# MB_RELAY.net
KiCad netlist of a schematic drawn in Altium Designer
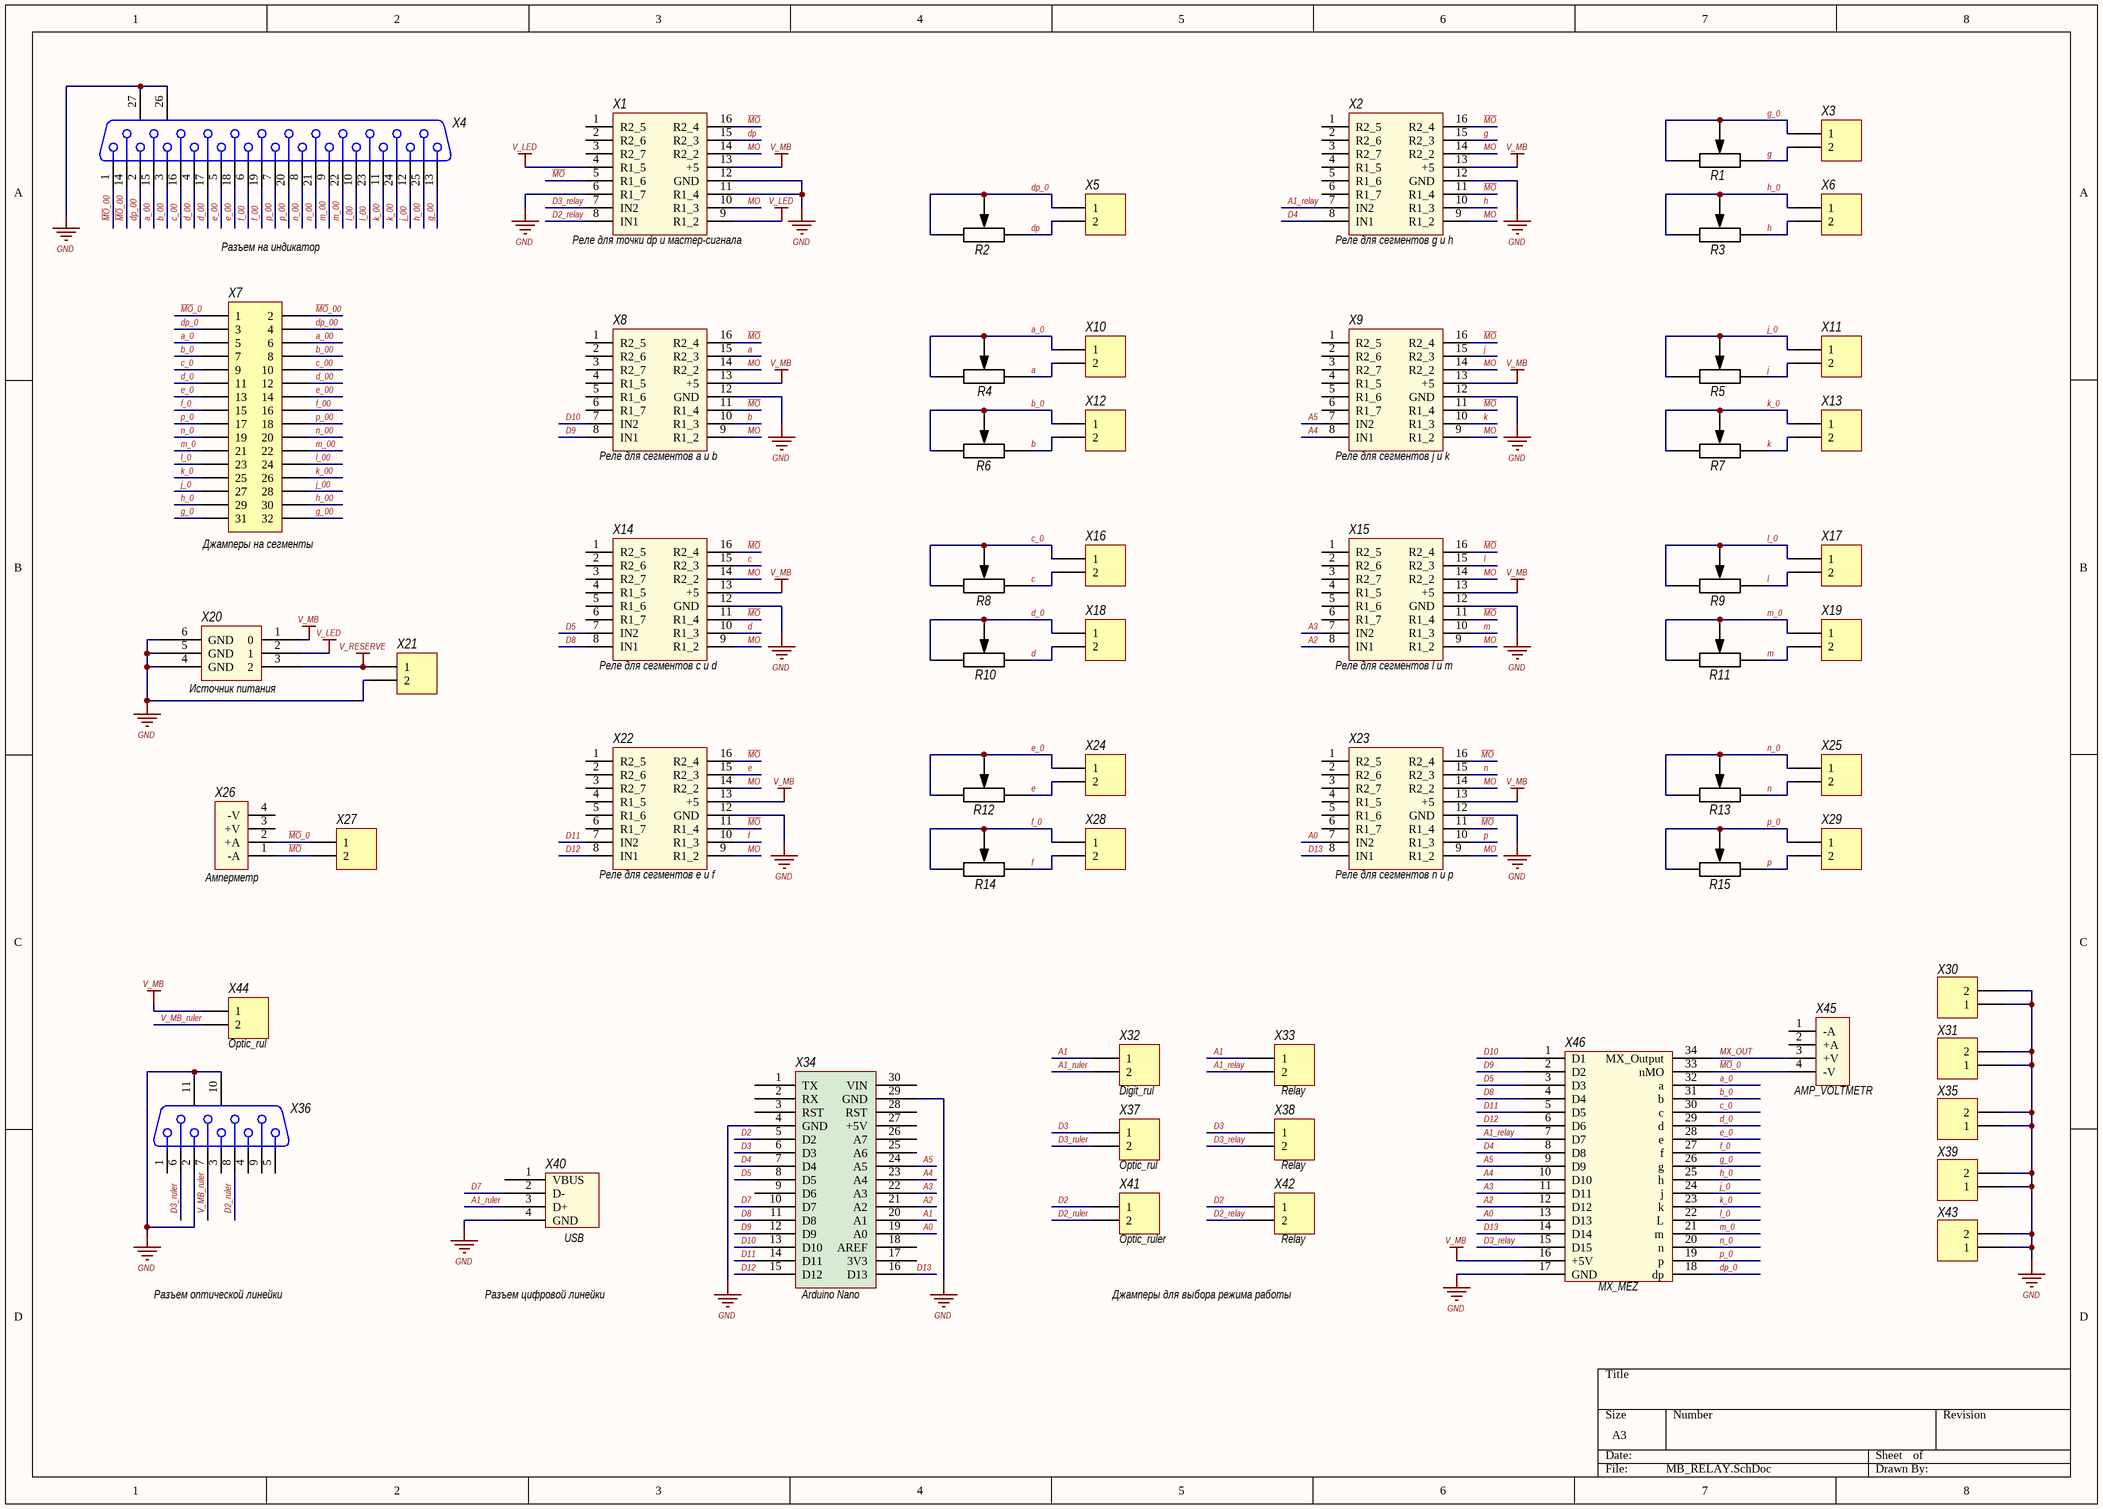
[diagram p0: MB_RELAY.SchDoc]

(export (version "E")
  (design (tool "Eeschema 10.0.6"))
  (components
    (comp (ref "R1")
      (value "RES 3266W")
      (footprint "aab_Passive:RES 3266W")
      (libsource (lib "aab_Schlib") (part "RES 3266W"))
    )
    (comp (ref "R2")
      (value "RES 3266W")
      (footprint "aab_Passive:RES 3266W")
      (libsource (lib "aab_Schlib") (part "RES 3266W"))
    )
    (comp (ref "R3")
      (value "RES 3266W")
      (footprint "aab_Passive:RES 3266W")
      (libsource (lib "aab_Schlib") (part "RES 3266W"))
    )
    (comp (ref "R4")
      (value "Переменнный резистор для")
      (footprint "aab_Passive:RES 3266W")
      (libsource (lib "aab_Schlib") (part "RES 3266W"))
    )
    (comp (ref "R5")
      (value "RES 3266W")
      (footprint "aab_Passive:RES 3266W")
      (libsource (lib "aab_Schlib") (part "RES 3266W"))
    )
    (comp (ref "R6")
      (value "RES 3266W")
      (footprint "aab_Passive:RES 3266W")
      (libsource (lib "aab_Schlib") (part "RES 3266W"))
    )
    (comp (ref "R7")
      (value "RES 3266W")
      (footprint "aab_Passive:RES 3266W")
      (libsource (lib "aab_Schlib") (part "RES 3266W"))
    )
    (comp (ref "R8")
      (value "RES 3266W")
      (footprint "aab_Passive:RES 3266W")
      (libsource (lib "aab_Schlib") (part "RES 3266W"))
    )
    (comp (ref "R9")
      (value "RES 3266W")
      (footprint "aab_Passive:RES 3266W")
      (libsource (lib "aab_Schlib") (part "RES 3266W"))
    )
    (comp (ref "R10")
      (value "RES 3266W")
      (footprint "aab_Passive:RES 3266W")
      (libsource (lib "aab_Schlib") (part "RES 3266W"))
    )
    (comp (ref "R11")
      (value "RES 3266W")
      (footprint "aab_Passive:RES 3266W")
      (libsource (lib "aab_Schlib") (part "RES 3266W"))
    )
    (comp (ref "R12")
      (value "RES 3266W")
      (footprint "aab_Passive:RES 3266W")
      (libsource (lib "aab_Schlib") (part "RES 3266W"))
    )
    (comp (ref "R13")
      (value "RES 3266W")
      (footprint "aab_Passive:RES 3266W")
      (libsource (lib "aab_Schlib") (part "RES 3266W"))
    )
    (comp (ref "R14")
      (value "RES 3266W")
      (footprint "aab_Passive:RES 3266W")
      (libsource (lib "aab_Schlib") (part "RES 3266W"))
    )
    (comp (ref "R15")
      (value "RES 3266W")
      (footprint "aab_Passive:RES 3266W")
      (libsource (lib "aab_Schlib") (part "RES 3266W"))
    )
    (comp (ref "X1")
      (value "Реле для точки dp и мастер-сигнала")
      (footprint "MEZ_RELAY")
      (libsource (lib "msp_SchLib") (part "MEZ_RELAY"))
    )
    (comp (ref "X2")
      (value "Реле для сегментов g и h")
      (footprint "MEZ_RELAY")
      (libsource (lib "msp_SchLib") (part "MEZ_RELAY"))
    )
    (comp (ref "X3")
      (value "GND")
      (footprint "HDR1X2")
      (description "Header, 2-Pin")
      (fields (field (name "PUBLISHER") "Altium Limited"))
      (libsource (lib "") (part "Header 2_1"))
    )
    (comp (ref "X4")
      (value "D Connector 25")
      (footprint "DSUB1.385-2H25A")
      (description "Receptacle Assembly, 25 Position, Right Angle")
      (fields (field (name "PUBLISHER") "Altium Limited"))
      (libsource (lib "Miscellaneous Connectors") (part "D Connector 25"))
    )
    (comp (ref "X5")
      (value "GND")
      (footprint "HDR1X2")
      (description "Header, 2-Pin")
      (fields (field (name "PUBLISHER") "Altium Limited"))
      (libsource (lib "") (part "Header 2_1"))
    )
    (comp (ref "X6")
      (value "GND")
      (footprint "HDR1X2")
      (description "Header, 2-Pin")
      (fields (field (name "PUBLISHER") "Altium Limited"))
      (libsource (lib "") (part "Header 2_1"))
    )
    (comp (ref "X7")
      (value "Header 16X2")
      (footprint "HDR2X16")
      (description "Header, 16-Pin, Dual row")
      (fields (field (name "PUBLISHER") "Altium Limited"))
      (libsource (lib "Miscellaneous Connectors") (part "Header 16X2"))
    )
    (comp (ref "X8")
      (value "Реле для сегментов a и b")
      (footprint "MEZ_RELAY")
      (libsource (lib "msp_SchLib") (part "MEZ_RELAY"))
    )
    (comp (ref "X9")
      (value "Реле для сегментов j и k")
      (footprint "MEZ_RELAY")
      (libsource (lib "msp_SchLib") (part "MEZ_RELAY"))
    )
    (comp (ref "X10")
      (value "Header 2")
      (footprint "HDR1X2")
      (description "Header, 2-Pin")
      (fields (field (name "PUBLISHER") "Altium Limited"))
      (libsource (lib "") (part "Header 2_1"))
    )
    (comp (ref "X11")
      (value "Header 2")
      (footprint "HDR1X2")
      (description "Header, 2-Pin")
      (fields (field (name "PUBLISHER") "Altium Limited"))
      (libsource (lib "") (part "Header 2_1"))
    )
    (comp (ref "X12")
      (value "Header 2")
      (footprint "HDR1X2")
      (description "Header, 2-Pin")
      (fields (field (name "PUBLISHER") "Altium Limited"))
      (libsource (lib "") (part "Header 2_1"))
    )
    (comp (ref "X13")
      (value "Header 2")
      (footprint "HDR1X2")
      (description "Header, 2-Pin")
      (fields (field (name "PUBLISHER") "Altium Limited"))
      (libsource (lib "") (part "Header 2_1"))
    )
    (comp (ref "X14")
      (value "Реле для сегментов c и d")
      (footprint "MEZ_RELAY")
      (libsource (lib "msp_SchLib") (part "MEZ_RELAY"))
    )
    (comp (ref "X15")
      (value "Реле для сегментов l и m")
      (footprint "MEZ_RELAY")
      (libsource (lib "msp_SchLib") (part "MEZ_RELAY"))
    )
    (comp (ref "X16")
      (value "Header 2")
      (footprint "HDR1X2")
      (description "Header, 2-Pin")
      (fields (field (name "PUBLISHER") "Altium Limited"))
      (libsource (lib "") (part "Header 2_1"))
    )
    (comp (ref "X17")
      (value "GND")
      (footprint "HDR1X2")
      (description "Header, 2-Pin")
      (fields (field (name "PUBLISHER") "Altium Limited"))
      (libsource (lib "") (part "Header 2_1"))
    )
    (comp (ref "X18")
      (value "Header 2")
      (footprint "HDR1X2")
      (description "Header, 2-Pin")
      (fields (field (name "PUBLISHER") "Altium Limited"))
      (libsource (lib "") (part "Header 2_1"))
    )
    (comp (ref "X19")
      (value "GND")
      (footprint "HDR1X2")
      (description "Header, 2-Pin")
      (fields (field (name "PUBLISHER") "Altium Limited"))
      (libsource (lib "") (part "Header 2_1"))
    )
    (comp (ref "X20")
      (value "Источник питания")
      (footprint "vpl_Passive:POWER")
      (libsource (lib "msp_SchLib") (part "POWER"))
    )
    (comp (ref "X21")
      (value "Header 2")
      (footprint "HDR1X2")
      (description "Header, 2-Pin")
      (fields (field (name "PUBLISHER") "Altium Limited"))
      (libsource (lib "") (part "Header 2_1"))
    )
    (comp (ref "X22")
      (value "Реле для сегментов e и f")
      (footprint "MEZ_RELAY")
      (libsource (lib "msp_SchLib") (part "MEZ_RELAY"))
    )
    (comp (ref "X23")
      (value "Реле для сегментов n и p")
      (footprint "MEZ_RELAY")
      (libsource (lib "msp_SchLib") (part "MEZ_RELAY"))
    )
    (comp (ref "X24")
      (value "GND")
      (footprint "HDR1X2")
      (description "Header, 2-Pin")
      (fields (field (name "PUBLISHER") "Altium Limited"))
      (libsource (lib "") (part "Header 2_1"))
    )
    (comp (ref "X25")
      (value "GND")
      (footprint "HDR1X2")
      (description "Header, 2-Pin")
      (fields (field (name "PUBLISHER") "Altium Limited"))
      (libsource (lib "") (part "Header 2_1"))
    )
    (comp (ref "X26")
      (value "Амперметр")
      (footprint "vpl_Passive:AMP_VOLTMETER")
      (libsource (lib "") (part "AMP_VOLTMETR_1"))
    )
    (comp (ref "X27")
      (value "Header 2")
      (footprint "HDR1X2")
      (description "Header, 2-Pin")
      (fields (field (name "PUBLISHER") "Altium Limited"))
      (libsource (lib "") (part "Header 2_1"))
    )
    (comp (ref "X28")
      (value "GND")
      (footprint "HDR1X2")
      (description "Header, 2-Pin")
      (fields (field (name "PUBLISHER") "Altium Limited"))
      (libsource (lib "") (part "Header 2_1"))
    )
    (comp (ref "X29")
      (value "GND")
      (footprint "HDR1X2")
      (description "Header, 2-Pin")
      (fields (field (name "PUBLISHER") "Altium Limited"))
      (libsource (lib "") (part "Header 2_1"))
    )
    (comp (ref "X30")
      (value "Header 2")
      (footprint "HDR1X2")
      (description "Header, 2-Pin")
      (fields (field (name "PUBLISHER") "Altium Limited"))
      (libsource (lib "Miscellaneous Connectors") (part "Header 2"))
    )
    (comp (ref "X31")
      (value "GND")
      (footprint "HDR1X2")
      (description "Header, 2-Pin")
      (fields (field (name "PUBLISHER") "Altium Limited"))
      (libsource (lib "Miscellaneous Connectors") (part "Header 2"))
    )
    (comp (ref "X32")
      (value "Digit_rul")
      (footprint "HDR1X2")
      (description "Header, 2-Pin")
      (fields (field (name "PUBLISHER") "Altium Limited"))
      (libsource (lib "") (part "Header 2_1"))
    )
    (comp (ref "X33")
      (value "Relay")
      (footprint "HDR1X2")
      (description "Header, 2-Pin")
      (fields (field (name "PUBLISHER") "Altium Limited"))
      (libsource (lib "") (part "Header 2_1"))
    )
    (comp (ref "X34")
      (value "Arduino Nano")
      (footprint "PCBComponent_1")
      (libsource (lib "Nano") (part "Component_1"))
    )
    (comp (ref "X35")
      (value "GND")
      (footprint "HDR1X2")
      (description "Header, 2-Pin")
      (fields (field (name "PUBLISHER") "Altium Limited"))
      (libsource (lib "Miscellaneous Connectors") (part "Header 2"))
    )
    (comp (ref "X36")
      (value "D Connector 9")
      (footprint "DSUB1.385-2H9")
      (description "Receptacle Assembly, 9 Position, Right Angle")
      (fields (field (name "PUBLISHER") "Altium Limited"))
      (libsource (lib "Miscellaneous Connectors") (part "D Connector 9"))
    )
    (comp (ref "X37")
      (value "Optic_rul")
      (footprint "HDR1X2")
      (description "Header, 2-Pin")
      (fields (field (name "PUBLISHER") "Altium Limited"))
      (libsource (lib "") (part "Header 2_1"))
    )
    (comp (ref "X38")
      (value "Relay")
      (footprint "HDR1X2")
      (description "Header, 2-Pin")
      (fields (field (name "PUBLISHER") "Altium Limited"))
      (libsource (lib "") (part "Header 2_1"))
    )
    (comp (ref "X39")
      (value "GND")
      (footprint "HDR1X2")
      (description "Header, 2-Pin")
      (fields (field (name "PUBLISHER") "Altium Limited"))
      (libsource (lib "Miscellaneous Connectors") (part "Header 2"))
    )
    (comp (ref "X40") (value "USB") (footprint "USB") (libsource (lib "msp_SchLib") (part "USB")))
    (comp (ref "X41")
      (value "Optic_ruler")
      (footprint "HDR1X2")
      (description "Header, 2-Pin")
      (fields (field (name "PUBLISHER") "Altium Limited"))
      (libsource (lib "") (part "Header 2_1"))
    )
    (comp (ref "X42")
      (value "Relay")
      (footprint "HDR1X2")
      (description "Header, 2-Pin")
      (fields (field (name "PUBLISHER") "Altium Limited"))
      (libsource (lib "") (part "Header 2_1"))
    )
    (comp (ref "X43")
      (value "GND")
      (footprint "HDR1X2")
      (description "Header, 2-Pin")
      (fields (field (name "PUBLISHER") "Altium Limited"))
      (libsource (lib "Miscellaneous Connectors") (part "Header 2"))
    )
    (comp (ref "X44")
      (value "Optic_rul")
      (footprint "HDR1X2")
      (description "Header, 2-Pin")
      (fields (field (name "PUBLISHER") "Altium Limited"))
      (libsource (lib "") (part "Header 2_1"))
    )
    (comp (ref "X45")
      (value "AMP_VOLTMETR")
      (footprint "AMP_VOLTMETR")
      (libsource (lib "msp_SchLib") (part "AMP_VOLTMETR"))
    )
    (comp (ref "X46") (value "MX_MEZ") (footprint "MX_MEZ") (libsource (lib "msp_SchLib") (part "MX_MEZ")))
  )
  (nets
    (net (code "1") (name "/A0") (class "Default")
      (node (ref "X23") (pin "7") (pinfunction "IN2_7") (pintype "passive"))
      (node (ref "X34") (pin "19") (pinfunction "A0_19") (pintype "passive"))
      (node (ref "X46") (pin "13") (pinfunction "D13_13") (pintype "passive"))
    )
    (net (code "2") (name "/A1") (class "Default")
      (node (ref "X32") (pin "1") (pinfunction "1_1") (pintype "passive"))
      (node (ref "X33") (pin "1") (pinfunction "1_1") (pintype "passive"))
      (node (ref "X34") (pin "20") (pinfunction "A1_20") (pintype "passive"))
    )
    (net (code "3") (name "/A1_relay") (class "Default")
      (node (ref "X2") (pin "7") (pinfunction "IN2_7") (pintype "passive"))
      (node (ref "X33") (pin "2") (pinfunction "2_2") (pintype "passive"))
      (node (ref "X46") (pin "7") (pinfunction "D7_7") (pintype "passive"))
    )
    (net (code "4") (name "/A1_ruler") (class "Default")
      (node (ref "X32") (pin "2") (pinfunction "2_2") (pintype "passive"))
      (node (ref "X40") (pin "3") (pinfunction "D+_3") (pintype "passive"))
    )
    (net (code "5") (name "/A2") (class "Default")
      (node (ref "X15") (pin "8") (pinfunction "IN1_8") (pintype "passive"))
      (node (ref "X34") (pin "21") (pinfunction "A2_21") (pintype "passive"))
      (node (ref "X46") (pin "12") (pinfunction "D12_12") (pintype "passive"))
    )
    (net (code "6") (name "/A3") (class "Default")
      (node (ref "X15") (pin "7") (pinfunction "IN2_7") (pintype "passive"))
      (node (ref "X34") (pin "22") (pinfunction "A3_22") (pintype "passive"))
      (node (ref "X46") (pin "11") (pinfunction "D11_11") (pintype "passive"))
    )
    (net (code "7") (name "/A4") (class "Default")
      (node (ref "X34") (pin "23") (pinfunction "A4_23") (pintype "passive"))
      (node (ref "X46") (pin "10") (pinfunction "D10_10") (pintype "passive"))
      (node (ref "X9") (pin "8") (pinfunction "IN1_8") (pintype "passive"))
    )
    (net (code "8") (name "/A5") (class "Default")
      (node (ref "X34") (pin "24") (pinfunction "A5_24") (pintype "passive"))
      (node (ref "X46") (pin "9") (pinfunction "D9_9") (pintype "passive"))
      (node (ref "X9") (pin "7") (pinfunction "IN2_7") (pintype "passive"))
    )
    (net (code "9") (name "/D2") (class "Default")
      (node (ref "X34") (pin "5") (pinfunction "D2_5") (pintype "passive"))
      (node (ref "X41") (pin "1") (pinfunction "1_1") (pintype "passive"))
      (node (ref "X42") (pin "1") (pinfunction "1_1") (pintype "passive"))
    )
    (net (code "10") (name "/D2_relay") (class "Default")
      (node (ref "X1") (pin "8") (pinfunction "IN1_8") (pintype "passive"))
      (node (ref "X42") (pin "2") (pinfunction "2_2") (pintype "passive"))
    )
    (net (code "11") (name "/D2_ruler") (class "Default")
      (node (ref "X36") (pin "8") (pinfunction "8_8") (pintype "passive"))
      (node (ref "X41") (pin "2") (pinfunction "2_2") (pintype "passive"))
    )
    (net (code "12") (name "/D3") (class "Default")
      (node (ref "X34") (pin "6") (pinfunction "D3_6") (pintype "passive"))
      (node (ref "X37") (pin "1") (pinfunction "1_1") (pintype "passive"))
      (node (ref "X38") (pin "1") (pinfunction "1_1") (pintype "passive"))
    )
    (net (code "13") (name "/D3_relay") (class "Default")
      (node (ref "X1") (pin "7") (pinfunction "IN2_7") (pintype "passive"))
      (node (ref "X38") (pin "2") (pinfunction "2_2") (pintype "passive"))
      (node (ref "X46") (pin "15") (pinfunction "D15_15") (pintype "passive"))
    )
    (net (code "14") (name "/D3_ruler") (class "Default")
      (node (ref "X36") (pin "6") (pinfunction "6_6") (pintype "passive"))
      (node (ref "X37") (pin "2") (pinfunction "2_2") (pintype "passive"))
    )
    (net (code "15") (name "/D4") (class "Default")
      (node (ref "X2") (pin "8") (pinfunction "IN1_8") (pintype "passive"))
      (node (ref "X34") (pin "7") (pinfunction "D4_7") (pintype "passive"))
      (node (ref "X46") (pin "8") (pinfunction "D8_8") (pintype "passive"))
    )
    (net (code "16") (name "/D5") (class "Default")
      (node (ref "X14") (pin "7") (pinfunction "IN2_7") (pintype "passive"))
      (node (ref "X34") (pin "8") (pinfunction "D5_8") (pintype "passive"))
      (node (ref "X46") (pin "3") (pinfunction "D3_3") (pintype "passive"))
    )
    (net (code "17") (name "/D7") (class "Default")
      (node (ref "X34") (pin "10") (pinfunction "D7_10") (pintype "passive"))
      (node (ref "X40") (pin "2") (pinfunction "D-_2") (pintype "passive"))
    )
    (net (code "18") (name "/D8") (class "Default")
      (node (ref "X14") (pin "8") (pinfunction "IN1_8") (pintype "passive"))
      (node (ref "X34") (pin "11") (pinfunction "D8_11") (pintype "passive"))
      (node (ref "X46") (pin "4") (pinfunction "D4_4") (pintype "passive"))
    )
    (net (code "19") (name "/D9") (class "Default")
      (node (ref "X34") (pin "12") (pinfunction "D9_12") (pintype "passive"))
      (node (ref "X46") (pin "2") (pinfunction "D2_2") (pintype "passive"))
      (node (ref "X8") (pin "8") (pinfunction "IN1_8") (pintype "passive"))
    )
    (net (code "20") (name "/D10") (class "Default")
      (node (ref "X34") (pin "13") (pinfunction "D10_13") (pintype "passive"))
      (node (ref "X46") (pin "1") (pinfunction "D1_1") (pintype "passive"))
      (node (ref "X8") (pin "7") (pinfunction "IN2_7") (pintype "passive"))
    )
    (net (code "21") (name "/D11") (class "Default")
      (node (ref "X22") (pin "7") (pinfunction "IN2_7") (pintype "passive"))
      (node (ref "X34") (pin "14") (pinfunction "D11_14") (pintype "passive"))
      (node (ref "X46") (pin "5") (pinfunction "D5_5") (pintype "passive"))
    )
    (net (code "22") (name "/D12") (class "Default")
      (node (ref "X22") (pin "8") (pinfunction "IN1_8") (pintype "passive"))
      (node (ref "X34") (pin "15") (pinfunction "D12_15") (pintype "passive"))
      (node (ref "X46") (pin "6") (pinfunction "D6_6") (pintype "passive"))
    )
    (net (code "23") (name "/D13") (class "Default")
      (node (ref "X23") (pin "8") (pinfunction "IN1_8") (pintype "passive"))
      (node (ref "X34") (pin "16") (pinfunction "D13_16") (pintype "passive"))
      (node (ref "X46") (pin "14") (pinfunction "D14_14") (pintype "passive"))
    )
    (net (code "24") (name "/MO") (class "Default")
      (node (ref "X1") (pin "10") (pinfunction "R1_3_10") (pintype "passive"))
      (node (ref "X1") (pin "14") (pinfunction "R2_2_14") (pintype "passive"))
      (node (ref "X14") (pin "14") (pinfunction "R2_2_14") (pintype "passive"))
      (node (ref "X14") (pin "9") (pinfunction "R1_2_9") (pintype "passive"))
      (node (ref "X15") (pin "14") (pinfunction "R2_2_14") (pintype "passive"))
      (node (ref "X15") (pin "9") (pinfunction "R1_2_9") (pintype "passive"))
      (node (ref "X2") (pin "14") (pinfunction "R2_2_14") (pintype "passive"))
      (node (ref "X2") (pin "9") (pinfunction "R1_2_9") (pintype "passive"))
      (node (ref "X22") (pin "14") (pinfunction "R2_2_14") (pintype "passive"))
      (node (ref "X22") (pin "9") (pinfunction "R1_2_9") (pintype "passive"))
      (node (ref "X23") (pin "14") (pinfunction "R2_2_14") (pintype "passive"))
      (node (ref "X23") (pin "9") (pinfunction "R1_2_9") (pintype "passive"))
      (node (ref "X8") (pin "14") (pinfunction "R2_2_14") (pintype "passive"))
      (node (ref "X8") (pin "9") (pinfunction "R1_2_9") (pintype "passive"))
      (node (ref "X9") (pin "14") (pinfunction "R2_2_14") (pintype "passive"))
      (node (ref "X9") (pin "9") (pinfunction "R1_2_9") (pintype "passive"))
    )
    (net (code "25") (name "/MX_OUT") (class "Default")
      (node (ref "X45") (pin "3") (pinfunction "+V_3") (pintype "passive"))
      (node (ref "X46") (pin "34") (pinfunction "MX_Output_34") (pintype "passive"))
    )
    (net (code "26") (name "/V_MB_ruler") (class "Default")
      (node (ref "X36") (pin "7") (pinfunction "7_7") (pintype "passive"))
      (node (ref "X44") (pin "2") (pinfunction "2_2") (pintype "passive"))
    )
    (net (code "27") (name "/a") (class "Default")
      (node (ref "R4") (pin "3") (pinfunction "3_3") (pintype "passive"))
      (node (ref "X10") (pin "2") (pinfunction "2_2") (pintype "passive"))
      (node (ref "X8") (pin "15") (pinfunction "R2_3_15") (pintype "passive"))
    )
    (net (code "28") (name "/a_0") (class "Default")
      (node (ref "R4") (pin "1") (pinfunction "1_1") (pintype "passive"))
      (node (ref "R4") (pin "2") (pinfunction "2_2") (pintype "passive"))
      (node (ref "X10") (pin "1") (pinfunction "1_1") (pintype "passive"))
      (node (ref "X46") (pin "32") (pinfunction "a_32") (pintype "passive"))
      (node (ref "X7") (pin "5") (pinfunction "5_5") (pintype "passive"))
    )
    (net (code "29") (name "/a_00") (class "Default")
      (node (ref "X4") (pin "15") (pinfunction "15_15") (pintype "passive"))
      (node (ref "X7") (pin "6") (pinfunction "6_6") (pintype "passive"))
    )
    (net (code "30") (name "/b") (class "Default")
      (node (ref "R6") (pin "3") (pinfunction "3_3") (pintype "passive"))
      (node (ref "X12") (pin "2") (pinfunction "2_2") (pintype "passive"))
      (node (ref "X8") (pin "10") (pinfunction "R1_3_10") (pintype "passive"))
    )
    (net (code "31") (name "/b_0") (class "Default")
      (node (ref "R6") (pin "1") (pinfunction "1_1") (pintype "passive"))
      (node (ref "R6") (pin "2") (pinfunction "2_2") (pintype "passive"))
      (node (ref "X12") (pin "1") (pinfunction "1_1") (pintype "passive"))
      (node (ref "X46") (pin "31") (pinfunction "b_31") (pintype "passive"))
      (node (ref "X7") (pin "7") (pinfunction "7_7") (pintype "passive"))
    )
    (net (code "32") (name "/b_00") (class "Default")
      (node (ref "X4") (pin "3") (pinfunction "3_3") (pintype "passive"))
      (node (ref "X7") (pin "8") (pinfunction "8_8") (pintype "passive"))
    )
    (net (code "33") (name "/c") (class "Default")
      (node (ref "R8") (pin "3") (pinfunction "3_3") (pintype "passive"))
      (node (ref "X14") (pin "15") (pinfunction "R2_3_15") (pintype "passive"))
      (node (ref "X16") (pin "2") (pinfunction "2_2") (pintype "passive"))
    )
    (net (code "34") (name "/c_0") (class "Default")
      (node (ref "R8") (pin "1") (pinfunction "1_1") (pintype "passive"))
      (node (ref "R8") (pin "2") (pinfunction "2_2") (pintype "passive"))
      (node (ref "X16") (pin "1") (pinfunction "1_1") (pintype "passive"))
      (node (ref "X46") (pin "30") (pinfunction "c_30") (pintype "passive"))
      (node (ref "X7") (pin "9") (pinfunction "9_9") (pintype "passive"))
    )
    (net (code "35") (name "/c_00") (class "Default")
      (node (ref "X4") (pin "16") (pinfunction "16_16") (pintype "passive"))
      (node (ref "X7") (pin "10") (pinfunction "10_10") (pintype "passive"))
    )
    (net (code "36") (name "/d") (class "Default")
      (node (ref "R10") (pin "3") (pinfunction "3_3") (pintype "passive"))
      (node (ref "X14") (pin "10") (pinfunction "R1_3_10") (pintype "passive"))
      (node (ref "X18") (pin "2") (pinfunction "2_2") (pintype "passive"))
    )
    (net (code "37") (name "/d_00") (class "Default")
      (node (ref "X4") (pin "17") (pinfunction "17_17") (pintype "passive"))
      (node (ref "X4") (pin "4") (pinfunction "4_4") (pintype "passive"))
      (node (ref "X7") (pin "12") (pinfunction "12_12") (pintype "passive"))
    )
    (net (code "38") (name "/d_0") (class "Default")
      (node (ref "R10") (pin "1") (pinfunction "1_1") (pintype "passive"))
      (node (ref "R10") (pin "2") (pinfunction "2_2") (pintype "passive"))
      (node (ref "X18") (pin "1") (pinfunction "1_1") (pintype "passive"))
      (node (ref "X46") (pin "29") (pinfunction "d_29") (pintype "passive"))
      (node (ref "X7") (pin "11") (pinfunction "11_11") (pintype "passive"))
    )
    (net (code "39") (name "/dp") (class "Default")
      (node (ref "R2") (pin "3") (pinfunction "3_3") (pintype "passive"))
      (node (ref "X1") (pin "15") (pinfunction "R2_3_15") (pintype "passive"))
      (node (ref "X5") (pin "2") (pinfunction "2_2") (pintype "passive"))
    )
    (net (code "40") (name "/dp_0") (class "Default")
      (node (ref "R2") (pin "1") (pinfunction "1_1") (pintype "passive"))
      (node (ref "R2") (pin "2") (pinfunction "2_2") (pintype "passive"))
      (node (ref "X46") (pin "18") (pinfunction "dp_18") (pintype "passive"))
      (node (ref "X5") (pin "1") (pinfunction "1_1") (pintype "passive"))
      (node (ref "X7") (pin "3") (pinfunction "3_3") (pintype "passive"))
    )
    (net (code "41") (name "/dp_00") (class "Default")
      (node (ref "X4") (pin "2") (pinfunction "2_2") (pintype "passive"))
      (node (ref "X7") (pin "4") (pinfunction "4_4") (pintype "passive"))
    )
    (net (code "42") (name "/e") (class "Default")
      (node (ref "R12") (pin "3") (pinfunction "3_3") (pintype "passive"))
      (node (ref "X22") (pin "15") (pinfunction "R2_3_15") (pintype "passive"))
      (node (ref "X24") (pin "2") (pinfunction "2_2") (pintype "passive"))
    )
    (net (code "43") (name "/e_0") (class "Default")
      (node (ref "R12") (pin "1") (pinfunction "1_1") (pintype "passive"))
      (node (ref "R12") (pin "2") (pinfunction "2_2") (pintype "passive"))
      (node (ref "X24") (pin "1") (pinfunction "1_1") (pintype "passive"))
      (node (ref "X46") (pin "28") (pinfunction "e_28") (pintype "passive"))
      (node (ref "X7") (pin "13") (pinfunction "13_13") (pintype "passive"))
    )
    (net (code "44") (name "/e_00") (class "Default")
      (node (ref "X4") (pin "18") (pinfunction "18_18") (pintype "passive"))
      (node (ref "X4") (pin "5") (pinfunction "5_5") (pintype "passive"))
      (node (ref "X7") (pin "14") (pinfunction "14_14") (pintype "passive"))
    )
    (net (code "45") (name "/f") (class "Default")
      (node (ref "R14") (pin "3") (pinfunction "3_3") (pintype "passive"))
      (node (ref "X22") (pin "10") (pinfunction "R1_3_10") (pintype "passive"))
      (node (ref "X28") (pin "2") (pinfunction "2_2") (pintype "passive"))
    )
    (net (code "46") (name "/f_0") (class "Default")
      (node (ref "R14") (pin "1") (pinfunction "1_1") (pintype "passive"))
      (node (ref "R14") (pin "2") (pinfunction "2_2") (pintype "passive"))
      (node (ref "X28") (pin "1") (pinfunction "1_1") (pintype "passive"))
      (node (ref "X46") (pin "27") (pinfunction "f_27") (pintype "passive"))
      (node (ref "X7") (pin "15") (pinfunction "15_15") (pintype "passive"))
    )
    (net (code "47") (name "/f_00") (class "Default")
      (node (ref "X4") (pin "19") (pinfunction "19_19") (pintype "passive"))
      (node (ref "X4") (pin "6") (pinfunction "6_6") (pintype "passive"))
      (node (ref "X7") (pin "16") (pinfunction "16_16") (pintype "passive"))
    )
    (net (code "48") (name "/g") (class "Default")
      (node (ref "R1") (pin "3") (pinfunction "3_3") (pintype "passive"))
      (node (ref "X2") (pin "15") (pinfunction "R2_3_15") (pintype "passive"))
      (node (ref "X3") (pin "2") (pinfunction "2_2") (pintype "passive"))
    )
    (net (code "49") (name "/g_0") (class "Default")
      (node (ref "R1") (pin "1") (pinfunction "1_1") (pintype "passive"))
      (node (ref "R1") (pin "2") (pinfunction "2_2") (pintype "passive"))
      (node (ref "X3") (pin "1") (pinfunction "1_1") (pintype "passive"))
      (node (ref "X46") (pin "26") (pinfunction "g_26") (pintype "passive"))
      (node (ref "X7") (pin "31") (pinfunction "31_31") (pintype "passive"))
    )
    (net (code "50") (name "/g_00") (class "Default")
      (node (ref "X4") (pin "13") (pinfunction "13_13") (pintype "passive"))
      (node (ref "X7") (pin "32") (pinfunction "32_32") (pintype "passive"))
    )
    (net (code "51") (name "/h") (class "Default")
      (node (ref "R3") (pin "3") (pinfunction "3_3") (pintype "passive"))
      (node (ref "X2") (pin "10") (pinfunction "R1_3_10") (pintype "passive"))
      (node (ref "X6") (pin "2") (pinfunction "2_2") (pintype "passive"))
    )
    (net (code "52") (name "/h_0") (class "Default")
      (node (ref "R3") (pin "1") (pinfunction "1_1") (pintype "passive"))
      (node (ref "R3") (pin "2") (pinfunction "2_2") (pintype "passive"))
      (node (ref "X46") (pin "25") (pinfunction "h_25") (pintype "passive"))
      (node (ref "X6") (pin "1") (pinfunction "1_1") (pintype "passive"))
      (node (ref "X7") (pin "29") (pinfunction "29_29") (pintype "passive"))
    )
    (net (code "53") (name "/h_00") (class "Default")
      (node (ref "X4") (pin "25") (pinfunction "25_25") (pintype "passive"))
      (node (ref "X7") (pin "30") (pinfunction "30_30") (pintype "passive"))
    )
    (net (code "54") (name "/j") (class "Default")
      (node (ref "R5") (pin "3") (pinfunction "3_3") (pintype "passive"))
      (node (ref "X11") (pin "2") (pinfunction "2_2") (pintype "passive"))
      (node (ref "X9") (pin "15") (pinfunction "R2_3_15") (pintype "passive"))
    )
    (net (code "55") (name "/j_00") (class "Default")
      (node (ref "X4") (pin "12") (pinfunction "12_12") (pintype "passive"))
      (node (ref "X7") (pin "28") (pinfunction "28_28") (pintype "passive"))
    )
    (net (code "56") (name "/j_0") (class "Default")
      (node (ref "R5") (pin "1") (pinfunction "1_1") (pintype "passive"))
      (node (ref "R5") (pin "2") (pinfunction "2_2") (pintype "passive"))
      (node (ref "X11") (pin "1") (pinfunction "1_1") (pintype "passive"))
      (node (ref "X46") (pin "24") (pinfunction "j_24") (pintype "passive"))
      (node (ref "X7") (pin "27") (pinfunction "27_27") (pintype "passive"))
    )
    (net (code "57") (name "/k") (class "Default")
      (node (ref "R7") (pin "3") (pinfunction "3_3") (pintype "passive"))
      (node (ref "X13") (pin "2") (pinfunction "2_2") (pintype "passive"))
      (node (ref "X9") (pin "10") (pinfunction "R1_3_10") (pintype "passive"))
    )
    (net (code "58") (name "/k_0") (class "Default")
      (node (ref "R7") (pin "1") (pinfunction "1_1") (pintype "passive"))
      (node (ref "R7") (pin "2") (pinfunction "2_2") (pintype "passive"))
      (node (ref "X13") (pin "1") (pinfunction "1_1") (pintype "passive"))
      (node (ref "X46") (pin "23") (pinfunction "k_23") (pintype "passive"))
      (node (ref "X7") (pin "25") (pinfunction "25_25") (pintype "passive"))
    )
    (net (code "59") (name "/k_00") (class "Default")
      (node (ref "X4") (pin "11") (pinfunction "11_11") (pintype "passive"))
      (node (ref "X4") (pin "24") (pinfunction "24_24") (pintype "passive"))
      (node (ref "X7") (pin "26") (pinfunction "26_26") (pintype "passive"))
    )
    (net (code "60") (name "/l") (class "Default")
      (node (ref "R9") (pin "3") (pinfunction "3_3") (pintype "passive"))
      (node (ref "X15") (pin "15") (pinfunction "R2_3_15") (pintype "passive"))
      (node (ref "X17") (pin "2") (pinfunction "2_2") (pintype "passive"))
    )
    (net (code "61") (name "/l_00") (class "Default")
      (node (ref "X4") (pin "10") (pinfunction "10_10") (pintype "passive"))
      (node (ref "X4") (pin "23") (pinfunction "23_23") (pintype "passive"))
      (node (ref "X7") (pin "24") (pinfunction "24_24") (pintype "passive"))
    )
    (net (code "62") (name "/l_0") (class "Default")
      (node (ref "R9") (pin "1") (pinfunction "1_1") (pintype "passive"))
      (node (ref "R9") (pin "2") (pinfunction "2_2") (pintype "passive"))
      (node (ref "X17") (pin "1") (pinfunction "1_1") (pintype "passive"))
      (node (ref "X46") (pin "22") (pinfunction "L_22") (pintype "passive"))
      (node (ref "X7") (pin "23") (pinfunction "23_23") (pintype "passive"))
    )
    (net (code "63") (name "/m") (class "Default")
      (node (ref "R11") (pin "3") (pinfunction "3_3") (pintype "passive"))
      (node (ref "X15") (pin "10") (pinfunction "R1_3_10") (pintype "passive"))
      (node (ref "X19") (pin "2") (pinfunction "2_2") (pintype "passive"))
    )
    (net (code "64") (name "/m_00") (class "Default")
      (node (ref "X4") (pin "22") (pinfunction "22_22") (pintype "passive"))
      (node (ref "X4") (pin "9") (pinfunction "9_9") (pintype "passive"))
      (node (ref "X7") (pin "22") (pinfunction "22_22") (pintype "passive"))
    )
    (net (code "65") (name "/m_0") (class "Default")
      (node (ref "R11") (pin "1") (pinfunction "1_1") (pintype "passive"))
      (node (ref "R11") (pin "2") (pinfunction "2_2") (pintype "passive"))
      (node (ref "X19") (pin "1") (pinfunction "1_1") (pintype "passive"))
      (node (ref "X46") (pin "21") (pinfunction "m_21") (pintype "passive"))
      (node (ref "X7") (pin "21") (pinfunction "21_21") (pintype "passive"))
    )
    (net (code "66") (name "/n") (class "Default")
      (node (ref "R13") (pin "3") (pinfunction "3_3") (pintype "passive"))
      (node (ref "X23") (pin "15") (pinfunction "R2_3_15") (pintype "passive"))
      (node (ref "X25") (pin "2") (pinfunction "2_2") (pintype "passive"))
    )
    (net (code "67") (name "/n_00") (class "Default")
      (node (ref "X4") (pin "21") (pinfunction "21_21") (pintype "passive"))
      (node (ref "X4") (pin "8") (pinfunction "8_8") (pintype "passive"))
      (node (ref "X7") (pin "20") (pinfunction "20_20") (pintype "passive"))
    )
    (net (code "68") (name "/n_0") (class "Default")
      (node (ref "R13") (pin "1") (pinfunction "1_1") (pintype "passive"))
      (node (ref "R13") (pin "2") (pinfunction "2_2") (pintype "passive"))
      (node (ref "X25") (pin "1") (pinfunction "1_1") (pintype "passive"))
      (node (ref "X46") (pin "20") (pinfunction "n_20") (pintype "passive"))
      (node (ref "X7") (pin "19") (pinfunction "19_19") (pintype "passive"))
    )
    (net (code "69") (name "/p") (class "Default")
      (node (ref "R15") (pin "3") (pinfunction "3_3") (pintype "passive"))
      (node (ref "X23") (pin "10") (pinfunction "R1_3_10") (pintype "passive"))
      (node (ref "X29") (pin "2") (pinfunction "2_2") (pintype "passive"))
    )
    (net (code "70") (name "/p_0") (class "Default")
      (node (ref "R15") (pin "1") (pinfunction "1_1") (pintype "passive"))
      (node (ref "R15") (pin "2") (pinfunction "2_2") (pintype "passive"))
      (node (ref "X29") (pin "1") (pinfunction "1_1") (pintype "passive"))
      (node (ref "X46") (pin "19") (pinfunction "p_19") (pintype "passive"))
      (node (ref "X7") (pin "17") (pinfunction "17_17") (pintype "passive"))
    )
    (net (code "71") (name "/p_00") (class "Default")
      (node (ref "X4") (pin "20") (pinfunction "20_20") (pintype "passive"))
      (node (ref "X4") (pin "7") (pinfunction "7_7") (pintype "passive"))
      (node (ref "X7") (pin "18") (pinfunction "18_18") (pintype "passive"))
    )
    (net (code "72") (name "/~{MO}") (class "Default")
      (node (ref "X1") (pin "16") (pinfunction "R2_4_16") (pintype "passive"))
      (node (ref "X1") (pin "5") (pinfunction "R1_6_5") (pintype "passive"))
      (node (ref "X14") (pin "11") (pinfunction "R1_4_11") (pintype "passive"))
      (node (ref "X14") (pin "16") (pinfunction "R2_4_16") (pintype "passive"))
      (node (ref "X15") (pin "11") (pinfunction "R1_4_11") (pintype "passive"))
      (node (ref "X15") (pin "16") (pinfunction "R2_4_16") (pintype "passive"))
      (node (ref "X2") (pin "11") (pinfunction "R1_4_11") (pintype "passive"))
      (node (ref "X2") (pin "16") (pinfunction "R2_4_16") (pintype "passive"))
      (node (ref "X22") (pin "11") (pinfunction "R1_4_11") (pintype "passive"))
      (node (ref "X22") (pin "16") (pinfunction "R2_4_16") (pintype "passive"))
      (node (ref "X23") (pin "11") (pinfunction "R1_4_11") (pintype "passive"))
      (node (ref "X23") (pin "16") (pinfunction "R2_4_16") (pintype "passive"))
      (node (ref "X26") (pin "1") (pinfunction "-A_1") (pintype "passive"))
      (node (ref "X27") (pin "2") (pinfunction "2_2") (pintype "passive"))
      (node (ref "X8") (pin "11") (pinfunction "R1_4_11") (pintype "passive"))
      (node (ref "X8") (pin "16") (pinfunction "R2_4_16") (pintype "passive"))
      (node (ref "X9") (pin "11") (pinfunction "R1_4_11") (pintype "passive"))
      (node (ref "X9") (pin "16") (pinfunction "R2_4_16") (pintype "passive"))
    )
    (net (code "73") (name "/~{MO}_0") (class "Default")
      (node (ref "X26") (pin "2") (pinfunction "+A_2") (pintype "passive"))
      (node (ref "X27") (pin "1") (pinfunction "1_1") (pintype "passive"))
      (node (ref "X45") (pin "4") (pinfunction "-V_4") (pintype "passive"))
      (node (ref "X46") (pin "33") (pinfunction "nMO_33") (pintype "passive"))
      (node (ref "X7") (pin "1") (pinfunction "1_1") (pintype "passive"))
    )
    (net (code "74") (name "/~{MO}_00") (class "Default")
      (node (ref "X4") (pin "1") (pinfunction "1_1") (pintype "passive"))
      (node (ref "X4") (pin "14") (pinfunction "14_14") (pintype "passive"))
      (node (ref "X7") (pin "2") (pinfunction "2_2") (pintype "passive"))
    )
    (net (code "75") (name "GND") (class "Default")
      (node (ref "X1") (pin "11") (pinfunction "R1_4_11") (pintype "passive"))
      (node (ref "X1") (pin "12") (pinfunction "GND_12") (pintype "passive"))
      (node (ref "X1") (pin "6") (pinfunction "R1_7_6") (pintype "passive"))
      (node (ref "X14") (pin "12") (pinfunction "GND_12") (pintype "passive"))
      (node (ref "X15") (pin "12") (pinfunction "GND_12") (pintype "passive"))
      (node (ref "X2") (pin "12") (pinfunction "GND_12") (pintype "passive"))
      (node (ref "X20") (pin "4") (pinfunction "GND_4") (pintype "passive"))
      (node (ref "X20") (pin "5") (pinfunction "GND_5") (pintype "passive"))
      (node (ref "X20") (pin "6") (pinfunction "GND_6") (pintype "passive"))
      (node (ref "X21") (pin "2") (pinfunction "2_2") (pintype "passive"))
      (node (ref "X22") (pin "12") (pinfunction "GND_12") (pintype "passive"))
      (node (ref "X23") (pin "12") (pinfunction "GND_12") (pintype "passive"))
      (node (ref "X30") (pin "1") (pinfunction "1_1") (pintype "passive"))
      (node (ref "X30") (pin "2") (pinfunction "2_2") (pintype "passive"))
      (node (ref "X31") (pin "1") (pinfunction "1_1") (pintype "passive"))
      (node (ref "X31") (pin "2") (pinfunction "2_2") (pintype "passive"))
      (node (ref "X34") (pin "29") (pinfunction "GND_29") (pintype "passive"))
      (node (ref "X34") (pin "4") (pinfunction "GND_4") (pintype "passive"))
      (node (ref "X35") (pin "1") (pinfunction "1_1") (pintype "passive"))
      (node (ref "X35") (pin "2") (pinfunction "2_2") (pintype "passive"))
      (node (ref "X36") (pin "10") (pinfunction "MH1_10") (pintype "passive"))
      (node (ref "X36") (pin "11") (pinfunction "MH2_11") (pintype "passive"))
      (node (ref "X36") (pin "2") (pinfunction "2_2") (pintype "passive"))
      (node (ref "X39") (pin "1") (pinfunction "1_1") (pintype "passive"))
      (node (ref "X39") (pin "2") (pinfunction "2_2") (pintype "passive"))
      (node (ref "X4") (pin "26") (pinfunction "MH1_26") (pintype "passive"))
      (node (ref "X4") (pin "27") (pinfunction "MH2_27") (pintype "passive"))
      (node (ref "X40") (pin "4") (pinfunction "GND_4") (pintype "passive"))
      (node (ref "X43") (pin "1") (pinfunction "1_1") (pintype "passive"))
      (node (ref "X43") (pin "2") (pinfunction "2_2") (pintype "passive"))
      (node (ref "X46") (pin "17") (pinfunction "GND_17") (pintype "passive"))
      (node (ref "X8") (pin "12") (pinfunction "GND_12") (pintype "passive"))
      (node (ref "X9") (pin "12") (pinfunction "GND_12") (pintype "passive"))
    )
    (net (code "76") (name "V_LED") (class "Default")
      (node (ref "X1") (pin "4") (pinfunction "R1_5_4") (pintype "passive"))
      (node (ref "X1") (pin "9") (pinfunction "R1_2_9") (pintype "passive"))
      (node (ref "X20") (pin "2") (pinfunction "1_2") (pintype "passive"))
    )
    (net (code "77") (name "V_MB") (class "Default")
      (node (ref "X1") (pin "13") (pinfunction "+5_13") (pintype "passive"))
      (node (ref "X14") (pin "13") (pinfunction "+5_13") (pintype "passive"))
      (node (ref "X15") (pin "13") (pinfunction "+5_13") (pintype "passive"))
      (node (ref "X2") (pin "13") (pinfunction "+5_13") (pintype "passive"))
      (node (ref "X20") (pin "1") (pinfunction "0_1") (pintype "passive"))
      (node (ref "X22") (pin "13") (pinfunction "+5_13") (pintype "passive"))
      (node (ref "X23") (pin "13") (pinfunction "+5_13") (pintype "passive"))
      (node (ref "X44") (pin "1") (pinfunction "1_1") (pintype "passive"))
      (node (ref "X46") (pin "16") (pinfunction "+5V_16") (pintype "passive"))
      (node (ref "X8") (pin "13") (pinfunction "+5_13") (pintype "passive"))
      (node (ref "X9") (pin "13") (pinfunction "+5_13") (pintype "passive"))
    )
    (net (code "78") (name "V_RESERVE") (class "Default")
      (node (ref "X20") (pin "3") (pinfunction "2_3") (pintype "passive"))
      (node (ref "X21") (pin "1") (pinfunction "1_1") (pintype "passive"))
    )
    (net (code "79") (name "unconnected-(X1-R2_5-Pad1)") (class "Default")
      (node (ref "X1") (pin "1") (pinfunction "R2_5_1") (pintype "passive"))
    )
    (net (code "80") (name "unconnected-(X1-R2_6-Pad2)") (class "Default")
      (node (ref "X1") (pin "2") (pinfunction "R2_6_2") (pintype "passive"))
    )
    (net (code "81") (name "unconnected-(X1-R2_7-Pad3)") (class "Default")
      (node (ref "X1") (pin "3") (pinfunction "R2_7_3") (pintype "passive"))
    )
    (net (code "82") (name "unconnected-(X2-R1_5-Pad4)") (class "Default")
      (node (ref "X2") (pin "4") (pinfunction "R1_5_4") (pintype "passive"))
    )
    (net (code "83") (name "unconnected-(X2-R1_6-Pad5)") (class "Default")
      (node (ref "X2") (pin "5") (pinfunction "R1_6_5") (pintype "passive"))
    )
    (net (code "84") (name "unconnected-(X2-R1_7-Pad6)") (class "Default")
      (node (ref "X2") (pin "6") (pinfunction "R1_7_6") (pintype "passive"))
    )
    (net (code "85") (name "unconnected-(X2-R2_5-Pad1)") (class "Default")
      (node (ref "X2") (pin "1") (pinfunction "R2_5_1") (pintype "passive"))
    )
    (net (code "86") (name "unconnected-(X2-R2_6-Pad2)") (class "Default")
      (node (ref "X2") (pin "2") (pinfunction "R2_6_2") (pintype "passive"))
    )
    (net (code "87") (name "unconnected-(X2-R2_7-Pad3)") (class "Default")
      (node (ref "X2") (pin "3") (pinfunction "R2_7_3") (pintype "passive"))
    )
    (net (code "88") (name "unconnected-(X8-R1_5-Pad4)") (class "Default")
      (node (ref "X8") (pin "4") (pinfunction "R1_5_4") (pintype "passive"))
    )
    (net (code "89") (name "unconnected-(X8-R1_6-Pad5)") (class "Default")
      (node (ref "X8") (pin "5") (pinfunction "R1_6_5") (pintype "passive"))
    )
    (net (code "90") (name "unconnected-(X8-R1_7-Pad6)") (class "Default")
      (node (ref "X8") (pin "6") (pinfunction "R1_7_6") (pintype "passive"))
    )
    (net (code "91") (name "unconnected-(X8-R2_5-Pad1)") (class "Default")
      (node (ref "X8") (pin "1") (pinfunction "R2_5_1") (pintype "passive"))
    )
    (net (code "92") (name "unconnected-(X8-R2_6-Pad2)") (class "Default")
      (node (ref "X8") (pin "2") (pinfunction "R2_6_2") (pintype "passive"))
    )
    (net (code "93") (name "unconnected-(X8-R2_7-Pad3)") (class "Default")
      (node (ref "X8") (pin "3") (pinfunction "R2_7_3") (pintype "passive"))
    )
    (net (code "94") (name "unconnected-(X9-R1_5-Pad4)") (class "Default")
      (node (ref "X9") (pin "4") (pinfunction "R1_5_4") (pintype "passive"))
    )
    (net (code "95") (name "unconnected-(X9-R1_6-Pad5)") (class "Default")
      (node (ref "X9") (pin "5") (pinfunction "R1_6_5") (pintype "passive"))
    )
    (net (code "96") (name "unconnected-(X9-R1_7-Pad6)") (class "Default")
      (node (ref "X9") (pin "6") (pinfunction "R1_7_6") (pintype "passive"))
    )
    (net (code "97") (name "unconnected-(X9-R2_5-Pad1)") (class "Default")
      (node (ref "X9") (pin "1") (pinfunction "R2_5_1") (pintype "passive"))
    )
    (net (code "98") (name "unconnected-(X9-R2_6-Pad2)") (class "Default")
      (node (ref "X9") (pin "2") (pinfunction "R2_6_2") (pintype "passive"))
    )
    (net (code "99") (name "unconnected-(X9-R2_7-Pad3)") (class "Default")
      (node (ref "X9") (pin "3") (pinfunction "R2_7_3") (pintype "passive"))
    )
    (net (code "100") (name "unconnected-(X14-R1_5-Pad4)") (class "Default")
      (node (ref "X14") (pin "4") (pinfunction "R1_5_4") (pintype "passive"))
    )
    (net (code "101") (name "unconnected-(X14-R1_6-Pad5)") (class "Default")
      (node (ref "X14") (pin "5") (pinfunction "R1_6_5") (pintype "passive"))
    )
    (net (code "102") (name "unconnected-(X14-R1_7-Pad6)") (class "Default")
      (node (ref "X14") (pin "6") (pinfunction "R1_7_6") (pintype "passive"))
    )
    (net (code "103") (name "unconnected-(X14-R2_5-Pad1)") (class "Default")
      (node (ref "X14") (pin "1") (pinfunction "R2_5_1") (pintype "passive"))
    )
    (net (code "104") (name "unconnected-(X14-R2_6-Pad2)") (class "Default")
      (node (ref "X14") (pin "2") (pinfunction "R2_6_2") (pintype "passive"))
    )
    (net (code "105") (name "unconnected-(X14-R2_7-Pad3)") (class "Default")
      (node (ref "X14") (pin "3") (pinfunction "R2_7_3") (pintype "passive"))
    )
    (net (code "106") (name "unconnected-(X15-R1_5-Pad4)") (class "Default")
      (node (ref "X15") (pin "4") (pinfunction "R1_5_4") (pintype "passive"))
    )
    (net (code "107") (name "unconnected-(X15-R1_6-Pad5)") (class "Default")
      (node (ref "X15") (pin "5") (pinfunction "R1_6_5") (pintype "passive"))
    )
    (net (code "108") (name "unconnected-(X15-R1_7-Pad6)") (class "Default")
      (node (ref "X15") (pin "6") (pinfunction "R1_7_6") (pintype "passive"))
    )
    (net (code "109") (name "unconnected-(X15-R2_5-Pad1)") (class "Default")
      (node (ref "X15") (pin "1") (pinfunction "R2_5_1") (pintype "passive"))
    )
    (net (code "110") (name "unconnected-(X15-R2_6-Pad2)") (class "Default")
      (node (ref "X15") (pin "2") (pinfunction "R2_6_2") (pintype "passive"))
    )
    (net (code "111") (name "unconnected-(X15-R2_7-Pad3)") (class "Default")
      (node (ref "X15") (pin "3") (pinfunction "R2_7_3") (pintype "passive"))
    )
    (net (code "112") (name "unconnected-(X22-R1_5-Pad4)") (class "Default")
      (node (ref "X22") (pin "4") (pinfunction "R1_5_4") (pintype "passive"))
    )
    (net (code "113") (name "unconnected-(X22-R1_6-Pad5)") (class "Default")
      (node (ref "X22") (pin "5") (pinfunction "R1_6_5") (pintype "passive"))
    )
    (net (code "114") (name "unconnected-(X22-R1_7-Pad6)") (class "Default")
      (node (ref "X22") (pin "6") (pinfunction "R1_7_6") (pintype "passive"))
    )
    (net (code "115") (name "unconnected-(X22-R2_5-Pad1)") (class "Default")
      (node (ref "X22") (pin "1") (pinfunction "R2_5_1") (pintype "passive"))
    )
    (net (code "116") (name "unconnected-(X22-R2_6-Pad2)") (class "Default")
      (node (ref "X22") (pin "2") (pinfunction "R2_6_2") (pintype "passive"))
    )
    (net (code "117") (name "unconnected-(X22-R2_7-Pad3)") (class "Default")
      (node (ref "X22") (pin "3") (pinfunction "R2_7_3") (pintype "passive"))
    )
    (net (code "118") (name "unconnected-(X23-R1_5-Pad4)") (class "Default")
      (node (ref "X23") (pin "4") (pinfunction "R1_5_4") (pintype "passive"))
    )
    (net (code "119") (name "unconnected-(X23-R1_6-Pad5)") (class "Default")
      (node (ref "X23") (pin "5") (pinfunction "R1_6_5") (pintype "passive"))
    )
    (net (code "120") (name "unconnected-(X23-R1_7-Pad6)") (class "Default")
      (node (ref "X23") (pin "6") (pinfunction "R1_7_6") (pintype "passive"))
    )
    (net (code "121") (name "unconnected-(X23-R2_5-Pad1)") (class "Default")
      (node (ref "X23") (pin "1") (pinfunction "R2_5_1") (pintype "passive"))
    )
    (net (code "122") (name "unconnected-(X23-R2_6-Pad2)") (class "Default")
      (node (ref "X23") (pin "2") (pinfunction "R2_6_2") (pintype "passive"))
    )
    (net (code "123") (name "unconnected-(X23-R2_7-Pad3)") (class "Default")
      (node (ref "X23") (pin "3") (pinfunction "R2_7_3") (pintype "passive"))
    )
    (net (code "124") (name "unconnected-(X26-+V-Pad3)") (class "Default")
      (node (ref "X26") (pin "3") (pinfunction "+V_3") (pintype "passive"))
    )
    (net (code "125") (name "unconnected-(X26--V-Pad4)") (class "Default")
      (node (ref "X26") (pin "4") (pinfunction "-V_4") (pintype "passive"))
    )
    (net (code "126") (name "unconnected-(X34-+5V-Pad27)") (class "Default")
      (node (ref "X34") (pin "27") (pinfunction "+5V_27") (pintype "passive"))
    )
    (net (code "127") (name "unconnected-(X34-3V3-Pad17)") (class "Default")
      (node (ref "X34") (pin "17") (pinfunction "3V3_17") (pintype "passive"))
    )
    (net (code "128") (name "unconnected-(X34-A6-Pad25)") (class "Default")
      (node (ref "X34") (pin "25") (pinfunction "A6_25") (pintype "passive"))
    )
    (net (code "129") (name "unconnected-(X34-A7-Pad26)") (class "Default")
      (node (ref "X34") (pin "26") (pinfunction "A7_26") (pintype "passive"))
    )
    (net (code "130") (name "unconnected-(X34-AREF-Pad18)") (class "Default")
      (node (ref "X34") (pin "18") (pinfunction "AREF_18") (pintype "passive"))
    )
    (net (code "131") (name "unconnected-(X34-D6-Pad9)") (class "Default")
      (node (ref "X34") (pin "9") (pinfunction "D6_9") (pintype "passive"))
    )
    (net (code "132") (name "unconnected-(X34-RST-Pad3)") (class "Default")
      (node (ref "X34") (pin "3") (pinfunction "RST_3") (pintype "passive"))
    )
    (net (code "133") (name "unconnected-(X34-RST-Pad28)") (class "Default")
      (node (ref "X34") (pin "28") (pinfunction "RST_28") (pintype "passive"))
    )
    (net (code "134") (name "unconnected-(X34-RX-Pad2)") (class "Default")
      (node (ref "X34") (pin "2") (pinfunction "RX_2") (pintype "passive"))
    )
    (net (code "135") (name "unconnected-(X34-TX-Pad1)") (class "Default")
      (node (ref "X34") (pin "1") (pinfunction "TX_1") (pintype "passive"))
    )
    (net (code "136") (name "unconnected-(X34-VIN-Pad30)") (class "Default")
      (node (ref "X34") (pin "30") (pinfunction "VIN_30") (pintype "passive"))
    )
    (net (code "137") (name "unconnected-(X36-Pad1)") (class "Default")
      (node (ref "X36") (pin "1") (pinfunction "1_1") (pintype "passive"))
    )
    (net (code "138") (name "unconnected-(X36-Pad3)") (class "Default")
      (node (ref "X36") (pin "3") (pinfunction "3_3") (pintype "passive"))
    )
    (net (code "139") (name "unconnected-(X36-Pad4)") (class "Default")
      (node (ref "X36") (pin "4") (pinfunction "4_4") (pintype "passive"))
    )
    (net (code "140") (name "unconnected-(X36-Pad5)") (class "Default")
      (node (ref "X36") (pin "5") (pinfunction "5_5") (pintype "passive"))
    )
    (net (code "141") (name "unconnected-(X36-Pad9)") (class "Default")
      (node (ref "X36") (pin "9") (pinfunction "9_9") (pintype "passive"))
    )
    (net (code "142") (name "unconnected-(X40-VBUS-Pad1)") (class "Default")
      (node (ref "X40") (pin "1") (pinfunction "VBUS_1") (pintype "passive"))
    )
    (net (code "143") (name "unconnected-(X45-+A-Pad2)") (class "Default")
      (node (ref "X45") (pin "2") (pinfunction "+A_2") (pintype "passive"))
    )
    (net (code "144") (name "unconnected-(X45--A-Pad1)") (class "Default")
      (node (ref "X45") (pin "1") (pinfunction "-A_1") (pintype "passive"))
    )
  )
)
